# Sensores.net
KiCad netlist of a schematic drawn in Altium Designer
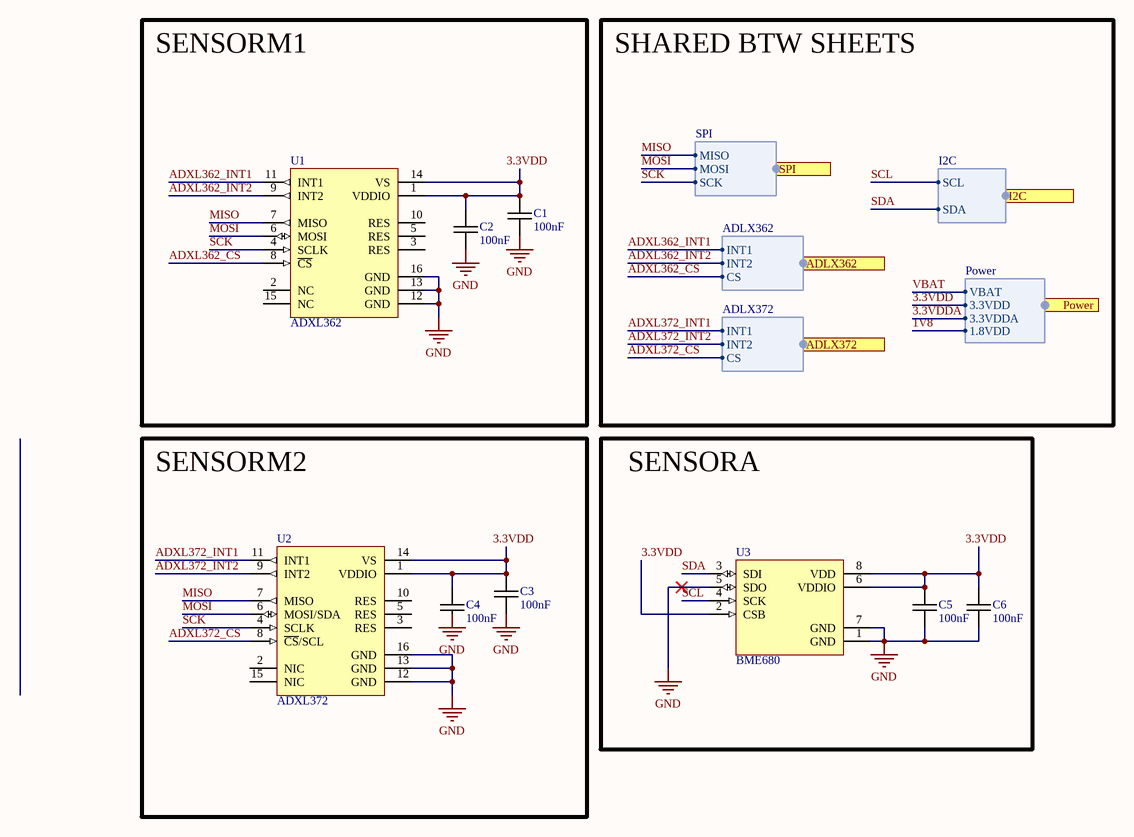
[diagram p0: Sensores.SchDoc]

(export (version "E")
  (design (tool "Eeschema 10.0.6"))
  (components
    (comp (ref "C1")
      (value "100nF")
      (footprint "0603C-GENERIC")
      (description "CAPACITOR 0603 CERAMIC")
      (fields (field (name "TOLERANCE") "±10%") (field (name "MANUFACTURER PART NUMBER") "C1608X7R1H103K"))
      (libsource (lib "vh_altium_library") (part "0603C-100NF-50V-X7R-TDK"))
    )
    (comp (ref "C2")
      (value "100nF")
      (footprint "0603C-GENERIC")
      (description "CAPACITOR 0603 CERAMIC")
      (fields (field (name "TOLERANCE") "±10%") (field (name "MANUFACTURER PART NUMBER") "C1608X7R1H103K"))
      (libsource (lib "vh_altium_library") (part "0603C-100NF-50V-X7R-TDK"))
    )
    (comp (ref "C3")
      (value "100nF")
      (footprint "0603C-GENERIC")
      (description "CAPACITOR 0603 CERAMIC")
      (fields (field (name "TOLERANCE") "±10%") (field (name "MANUFACTURER PART NUMBER") "C1608X7R1H103K"))
      (libsource (lib "vh_altium_library") (part "0603C-100NF-50V-X7R-TDK"))
    )
    (comp (ref "C4")
      (value "100nF")
      (footprint "0603C-GENERIC")
      (description "CAPACITOR 0603 CERAMIC")
      (fields (field (name "TOLERANCE") "±10%") (field (name "MANUFACTURER PART NUMBER") "C1608X7R1H103K"))
      (libsource (lib "vh_altium_library") (part "0603C-100NF-50V-X7R-TDK"))
    )
    (comp (ref "C5")
      (value "100nF")
      (footprint "0603C-GENERIC")
      (description "CAPACITOR 0603 CERAMIC")
      (fields (field (name "TOLERANCE") "±10%") (field (name "MANUFACTURER PART NUMBER") "C1608X7R1H103K"))
      (libsource (lib "vh_altium_library") (part "0603C-100NF-50V-X7R-TDK"))
    )
    (comp (ref "C6")
      (value "100nF")
      (footprint "0603C-GENERIC")
      (description "CAPACITOR 0603 CERAMIC")
      (fields (field (name "TOLERANCE") "±10%") (field (name "MANUFACTURER PART NUMBER") "C1608X7R1H103K"))
      (libsource (lib "vh_altium_library") (part "0603C-100NF-50V-X7R-TDK"))
    )
    (comp (ref "U1")
      (value "ADXL362")
      (footprint "LGA50P322X300X114-16N")
      (description "Micropower, 3-Axis, ±2 g/±4 g/±8 g Digital Output MEMS Accelerometer")
      (fields
        (field (name "MANUFACTURER") "Analog Devices")
        (field (name "PUBLISHER") "Nordic Semiconductor")
      )
      (libsource (lib "FEEL2020") (part "ADXL362"))
    )
    (comp (ref "U2")
      (value "ADXL372")
      (footprint "LGA50P322X300X114-16N")
      (description "Micropower, 3-Axis, ±200g digital output acelerometer")
      (fields
        (field (name "MANUFACTURER") "Analog Devices")
        (field (name "PUBLISHER") "Nordic Semiconductor")
      )
      (libsource (lib "FEEL2020") (part "ADXL372"))
    )
    (comp (ref "U3")
      (value "BME680")
      (footprint "BME680")
      (description "Low power gas, pressure, temperature & humidity sensor")
      (fields (field (name "MANUFACTURER") "Bosch") (field (name "PUBLISHER") "Nordic Semiconductor"))
      (libsource (lib "FEEL2020") (part "BME680"))
    )
  )
  (nets
    (net (code "7") (name "/3.3VDD") (class "Default")
      (node (ref "U3") (pin "2") (pinfunction "CSB_2") (pintype "input"))
    )
    (net (code "9") (name "/ADXL362_CS") (class "Default")
      (node (ref "U1") (pin "8") (pinfunction "~{CS}_8") (pintype "input"))
    )
    (net (code "10") (name "/ADXL362_INT1") (class "Default")
      (node (ref "U1") (pin "11") (pinfunction "INT1_11") (pintype "output"))
    )
    (net (code "11") (name "/ADXL362_INT2") (class "Default")
      (node (ref "U1") (pin "9") (pinfunction "INT2_9") (pintype "output"))
    )
    (net (code "12") (name "/ADXL372_CS") (class "Default")
      (node (ref "U2") (pin "8") (pinfunction "~{CS}/SCL_8") (pintype "input"))
    )
    (net (code "13") (name "/ADXL372_INT1") (class "Default")
      (node (ref "U2") (pin "11") (pinfunction "INT1_11") (pintype "output"))
    )
    (net (code "14") (name "/ADXL372_INT2") (class "Default")
      (node (ref "U2") (pin "9") (pinfunction "INT2_9") (pintype "output"))
    )
    (net (code "15") (name "/MISO") (class "Default")
      (node (ref "U1") (pin "7") (pinfunction "MISO_7") (pintype "output"))
      (node (ref "U2") (pin "7") (pinfunction "MISO_7") (pintype "output"))
    )
    (net (code "16") (name "/MOSI") (class "Default")
      (node (ref "U1") (pin "6") (pinfunction "MOSI_6") (pintype "bidirectional"))
      (node (ref "U2") (pin "6") (pinfunction "MOSI/SDA_6") (pintype "bidirectional"))
    )
    (net (code "17") (name "/SCK") (class "Default")
      (node (ref "U1") (pin "4") (pinfunction "SCLK_4") (pintype "input"))
      (node (ref "U2") (pin "4") (pinfunction "SCLK_4") (pintype "input"))
    )
    (net (code "18") (name "/SCL") (class "Default")
      (node (ref "U3") (pin "4") (pinfunction "SCK_4") (pintype "input"))
    )
    (net (code "19") (name "/SDA") (class "Default")
      (node (ref "U3") (pin "3") (pinfunction "SDI_3") (pintype "bidirectional"))
    )
    (net (code "26") (name "GND") (class "Default")
      (node (ref "C1") (pin "2") (pintype "passive"))
      (node (ref "C2") (pin "2") (pintype "passive"))
      (node (ref "C3") (pin "2") (pintype "passive"))
      (node (ref "C5") (pin "2") (pintype "passive"))
      (node (ref "C6") (pin "2") (pintype "passive"))
      (node (ref "U1") (pin "12") (pinfunction "GND_12") (pintype "power_in"))
      (node (ref "U1") (pin "13") (pinfunction "GND_13") (pintype "power_in"))
      (node (ref "U1") (pin "16") (pinfunction "GND_16") (pintype "power_in"))
      (node (ref "U2") (pin "12") (pinfunction "GND_12") (pintype "power_in"))
      (node (ref "U2") (pin "13") (pinfunction "GND_13") (pintype "power_in"))
      (node (ref "U2") (pin "16") (pinfunction "GND_16") (pintype "power_in"))
      (node (ref "U3") (pin "1") (pinfunction "GND_1") (pintype "power_in"))
      (node (ref "U3") (pin "5") (pinfunction "SDO_5") (pintype "bidirectional"))
      (node (ref "U3") (pin "7") (pinfunction "GND_7") (pintype "power_in"))
    )
    (net (code "27") (name "Net-(U1-VDDIO)") (class "Default")
      (node (ref "C1") (pin "1") (pintype "passive"))
      (node (ref "C2") (pin "1") (pintype "passive"))
      (node (ref "U1") (pin "1") (pinfunction "VDDIO_1") (pintype "power_in"))
      (node (ref "U1") (pin "14") (pinfunction "VS_14") (pintype "power_in"))
    )
    (net (code "28") (name "Net-(U2-VDDIO)") (class "Default")
      (node (ref "C3") (pin "1") (pintype "passive"))
      (node (ref "C4") (pin "1") (pintype "passive"))
      (node (ref "U2") (pin "1") (pinfunction "VDDIO_1") (pintype "power_in"))
      (node (ref "U2") (pin "14") (pinfunction "VS_14") (pintype "power_in"))
    )
    (net (code "29") (name "Net-(U3-VDD)") (class "Default")
      (node (ref "C5") (pin "1") (pintype "passive"))
      (node (ref "C6") (pin "1") (pintype "passive"))
      (node (ref "U3") (pin "6") (pinfunction "VDDIO_6") (pintype "power_in"))
      (node (ref "U3") (pin "8") (pinfunction "VDD_8") (pintype "power_in"))
    )
    (net (code "30") (name "unconnected-(C4-Pad2)") (class "Default")
      (node (ref "C4") (pin "2") (pintype "passive"))
    )
    (net (code "31") (name "unconnected-(U1-NC-Pad2)") (class "Default")
      (node (ref "U1") (pin "2") (pinfunction "NC_2") (pintype "passive"))
    )
    (net (code "32") (name "unconnected-(U1-NC-Pad15)") (class "Default")
      (node (ref "U1") (pin "15") (pinfunction "NC_15") (pintype "passive"))
    )
    (net (code "33") (name "unconnected-(U1-RES-Pad3)") (class "Default")
      (node (ref "U1") (pin "3") (pinfunction "RES_3") (pintype "passive"))
    )
    (net (code "34") (name "unconnected-(U1-RES-Pad5)") (class "Default")
      (node (ref "U1") (pin "5") (pinfunction "RES_5") (pintype "passive"))
    )
    (net (code "35") (name "unconnected-(U1-RES-Pad10)") (class "Default")
      (node (ref "U1") (pin "10") (pinfunction "RES_10") (pintype "passive"))
    )
    (net (code "36") (name "unconnected-(U2-NIC-Pad2)") (class "Default")
      (node (ref "U2") (pin "2") (pinfunction "NIC_2") (pintype "passive"))
    )
    (net (code "37") (name "unconnected-(U2-NIC-Pad15)") (class "Default")
      (node (ref "U2") (pin "15") (pinfunction "NIC_15") (pintype "passive"))
    )
    (net (code "38") (name "unconnected-(U2-RES-Pad3)") (class "Default")
      (node (ref "U2") (pin "3") (pinfunction "RES_3") (pintype "passive"))
    )
    (net (code "39") (name "unconnected-(U2-RES-Pad5)") (class "Default")
      (node (ref "U2") (pin "5") (pinfunction "RES_5") (pintype "passive"))
    )
    (net (code "40") (name "unconnected-(U2-RES-Pad10)") (class "Default")
      (node (ref "U2") (pin "10") (pinfunction "RES_10") (pintype "passive"))
    )
  )
)
